# hub75-Adapter_mkii.net
KiCad netlist of a schematic drawn in EAGLE
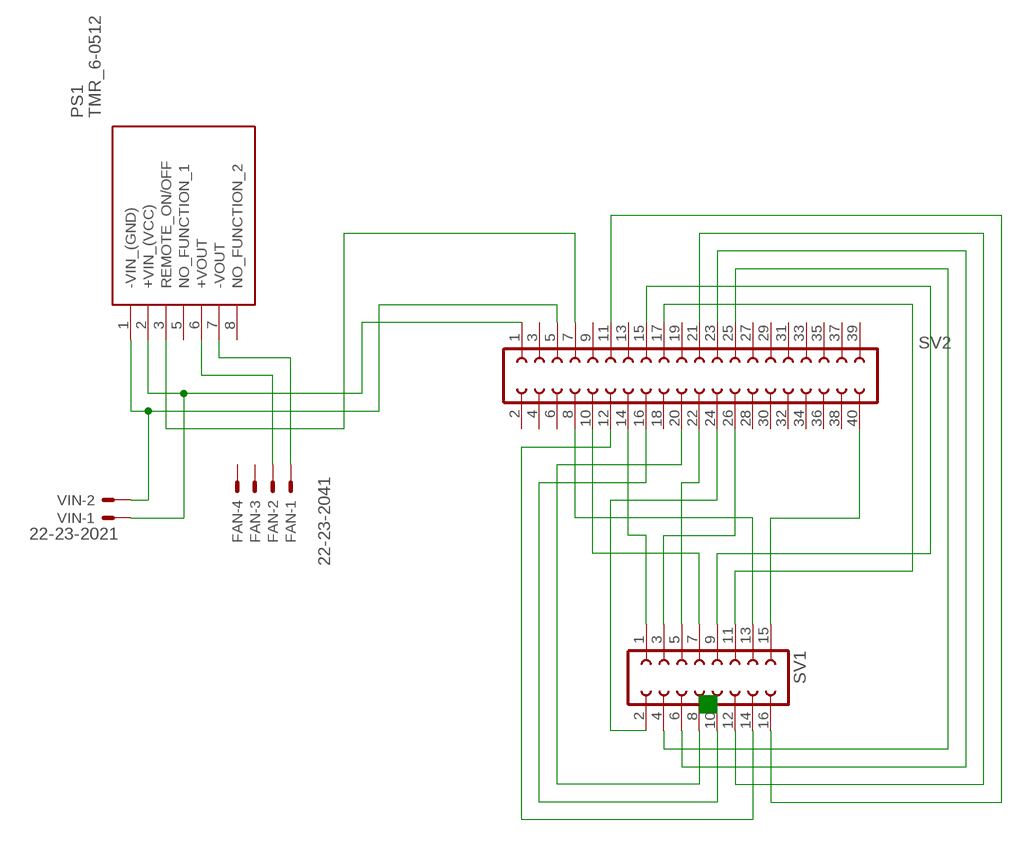
[diagram p0: schematic, sheet 1]

(export (version "E")
  (design (tool "Eeschema 10.0.6"))
  (components
    (comp (ref "FAN")
      (value "22-23-2041")
      (footprint "eagle-import:22-23-2041")
      (fields (field (name "MF") "MOLEX"))
      (libsource (lib "eagle-import") (part "22-23-2041"))
    )
    (comp (ref "PS1")
      (value "TMR_6-0512")
      (footprint "eagle-import:TMR-6")
      (fields
        (field (name "MANUFACTURER_PART_NUMBER") "TMR 6-0512")
        (field (name "MOUSER_PART_NUMBER") "495-TMR-6-0512")
      )
      (libsource (lib "eagle-import") (part "TMR_6-0512"))
    )
    (comp (ref "SV1")
      (value "FE08-2")
      (footprint "eagle-import:FE08-2")
      (libsource (lib "eagle-import") (part "FE08-2"))
    )
    (comp (ref "SV2")
      (value "FE20-2")
      (footprint "eagle-import:FE20-2")
      (libsource (lib "eagle-import") (part "FE20-2"))
    )
    (comp (ref "VIN")
      (value "22-23-2021")
      (footprint "eagle-import:22-23-2021")
      (fields (field (name "MF") "MOLEX"))
      (libsource (lib "eagle-import") (part "22-23-2021"))
    )
  )
  (nets
    (net (code "1") (name "Net-(FANA-S)") (class "Default")
      (node (ref "FAN") (pin "1") (pinfunction "S_1") (pintype "passive"))
      (node (ref "PS1") (pin "7") (pinfunction "-VOUT_7") (pintype "bidirectional"))
    )
    (net (code "2") (name "Net-(FANB-S)") (class "Default")
      (node (ref "FAN") (pin "2") (pinfunction "S_2") (pintype "passive"))
      (node (ref "PS1") (pin "6") (pinfunction "+VOUT_6") (pintype "bidirectional"))
    )
    (net (code "3") (name "Net-(PS1-+VIN_(VCC))") (class "Default")
      (node (ref "PS1") (pin "2") (pinfunction "+VIN_(VCC)_2") (pintype "bidirectional"))
      (node (ref "SV2") (pin "1") (pinfunction "1_1") (pintype "passive"))
      (node (ref "VIN") (pin "1") (pinfunction "S_1") (pintype "passive"))
    )
    (net (code "4") (name "Net-(PS1--VIN_(GND))") (class "Default")
      (node (ref "PS1") (pin "1") (pinfunction "-VIN_(GND)_1") (pintype "bidirectional"))
      (node (ref "SV2") (pin "5") (pinfunction "5_5") (pintype "passive"))
      (node (ref "VIN") (pin "2") (pinfunction "S_2") (pintype "passive"))
    )
    (net (code "5") (name "Net-(PS1-REMOTE_ON{slash}OFF)") (class "Default")
      (node (ref "PS1") (pin "3") (pinfunction "REMOTE_ON/OFF_3") (pintype "bidirectional"))
      (node (ref "SV2") (pin "7") (pinfunction "7_7") (pintype "passive"))
    )
    (net (code "6") (name "Net-(SV1-Pad1)") (class "Default")
      (node (ref "SV1") (pin "1") (pinfunction "1_1") (pintype "passive"))
      (node (ref "SV2") (pin "14") (pinfunction "14_14") (pintype "passive"))
    )
    (net (code "7") (name "Net-(SV1-Pad2)") (class "Default")
      (node (ref "SV1") (pin "2") (pinfunction "2_2") (pintype "passive"))
      (node (ref "SV2") (pin "24") (pinfunction "24_24") (pintype "passive"))
    )
    (net (code "8") (name "Net-(SV1-Pad3)") (class "Default")
      (node (ref "SV1") (pin "3") (pinfunction "3_3") (pintype "passive"))
      (node (ref "SV2") (pin "26") (pinfunction "26_26") (pintype "passive"))
    )
    (net (code "9") (name "Net-(SV1-Pad4)") (class "Default")
      (node (ref "SV1") (pin "4") (pinfunction "4_4") (pintype "passive"))
      (node (ref "SV2") (pin "25") (pinfunction "25_25") (pintype "passive"))
    )
    (net (code "10") (name "Net-(SV1-Pad5)") (class "Default")
      (node (ref "SV1") (pin "5") (pinfunction "5_5") (pintype "passive"))
      (node (ref "SV2") (pin "22") (pinfunction "22_22") (pintype "passive"))
    )
    (net (code "11") (name "Net-(SV1-Pad6)") (class "Default")
      (node (ref "SV1") (pin "6") (pinfunction "6_6") (pintype "passive"))
      (node (ref "SV2") (pin "23") (pinfunction "23_23") (pintype "passive"))
    )
    (net (code "12") (name "Net-(SV1-Pad7)") (class "Default")
      (node (ref "SV1") (pin "7") (pinfunction "7_7") (pintype "passive"))
      (node (ref "SV2") (pin "10") (pinfunction "10_10") (pintype "passive"))
    )
    (net (code "13") (name "Net-(SV1-Pad8)") (class "Default")
      (node (ref "SV1") (pin "8") (pinfunction "8_8") (pintype "passive"))
      (node (ref "SV2") (pin "20") (pinfunction "20_20") (pintype "passive"))
    )
    (net (code "14") (name "Net-(SV1-Pad9)") (class "Default")
      (node (ref "SV1") (pin "9") (pinfunction "9_9") (pintype "passive"))
      (node (ref "SV2") (pin "15") (pinfunction "15_15") (pintype "passive"))
    )
    (net (code "15") (name "Net-(SV1-Pad10)") (class "Default")
      (node (ref "SV1") (pin "10") (pinfunction "10_10") (pintype "passive"))
      (node (ref "SV2") (pin "16") (pinfunction "16_16") (pintype "passive"))
    )
    (net (code "16") (name "Net-(SV1-Pad11)") (class "Default")
      (node (ref "SV1") (pin "11") (pinfunction "11_11") (pintype "passive"))
      (node (ref "SV2") (pin "17") (pinfunction "17_17") (pintype "passive"))
    )
    (net (code "17") (name "Net-(SV1-Pad12)") (class "Default")
      (node (ref "SV1") (pin "12") (pinfunction "12_12") (pintype "passive"))
      (node (ref "SV2") (pin "21") (pinfunction "21_21") (pintype "passive"))
    )
    (net (code "18") (name "Net-(SV1-Pad13)") (class "Default")
      (node (ref "SV1") (pin "13") (pinfunction "13_13") (pintype "passive"))
      (node (ref "SV2") (pin "8") (pinfunction "8_8") (pintype "passive"))
    )
    (net (code "19") (name "Net-(SV1-Pad14)") (class "Default")
      (node (ref "SV1") (pin "14") (pinfunction "14_14") (pintype "passive"))
      (node (ref "SV2") (pin "12") (pinfunction "12_12") (pintype "passive"))
    )
    (net (code "20") (name "Net-(SV1-Pad15)") (class "Default")
      (node (ref "SV1") (pin "15") (pinfunction "15_15") (pintype "passive"))
      (node (ref "SV2") (pin "40") (pinfunction "40_40") (pintype "passive"))
    )
    (net (code "21") (name "Net-(SV1-Pad16)") (class "Default")
      (node (ref "SV1") (pin "16") (pinfunction "16_16") (pintype "passive"))
      (node (ref "SV2") (pin "11") (pinfunction "11_11") (pintype "passive"))
    )
    (net (code "22") (name "unconnected-(FANC-S-Pad3)") (class "Default")
      (node (ref "FAN") (pin "3") (pinfunction "S_3") (pintype "passive"))
    )
    (net (code "23") (name "unconnected-(FAND-S-Pad4)") (class "Default")
      (node (ref "FAN") (pin "4") (pinfunction "S_4") (pintype "passive"))
    )
    (net (code "24") (name "unconnected-(PS1-NO_FUNCTION_1-Pad5)") (class "Default")
      (node (ref "PS1") (pin "5") (pinfunction "NO_FUNCTION_1_5") (pintype "bidirectional"))
    )
    (net (code "25") (name "unconnected-(PS1-NO_FUNCTION_2-Pad8)") (class "Default")
      (node (ref "PS1") (pin "8") (pinfunction "NO_FUNCTION_2_8") (pintype "bidirectional"))
    )
    (net (code "26") (name "unconnected-(SV2-Pad2)") (class "Default")
      (node (ref "SV2") (pin "2") (pinfunction "2_2") (pintype "passive"))
    )
    (net (code "27") (name "unconnected-(SV2-Pad3)") (class "Default")
      (node (ref "SV2") (pin "3") (pinfunction "3_3") (pintype "passive"))
    )
    (net (code "28") (name "unconnected-(SV2-Pad4)") (class "Default")
      (node (ref "SV2") (pin "4") (pinfunction "4_4") (pintype "passive"))
    )
    (net (code "29") (name "unconnected-(SV2-Pad6)") (class "Default")
      (node (ref "SV2") (pin "6") (pinfunction "6_6") (pintype "passive"))
    )
    (net (code "30") (name "unconnected-(SV2-Pad9)") (class "Default")
      (node (ref "SV2") (pin "9") (pinfunction "9_9") (pintype "passive"))
    )
    (net (code "31") (name "unconnected-(SV2-Pad13)") (class "Default")
      (node (ref "SV2") (pin "13") (pinfunction "13_13") (pintype "passive"))
    )
    (net (code "32") (name "unconnected-(SV2-Pad18)") (class "Default")
      (node (ref "SV2") (pin "18") (pinfunction "18_18") (pintype "passive"))
    )
    (net (code "33") (name "unconnected-(SV2-Pad19)") (class "Default")
      (node (ref "SV2") (pin "19") (pinfunction "19_19") (pintype "passive"))
    )
    (net (code "34") (name "unconnected-(SV2-Pad27)") (class "Default")
      (node (ref "SV2") (pin "27") (pinfunction "27_27") (pintype "passive"))
    )
    (net (code "35") (name "unconnected-(SV2-Pad28)") (class "Default")
      (node (ref "SV2") (pin "28") (pinfunction "28_28") (pintype "passive"))
    )
    (net (code "36") (name "unconnected-(SV2-Pad29)") (class "Default")
      (node (ref "SV2") (pin "29") (pinfunction "29_29") (pintype "passive"))
    )
    (net (code "37") (name "unconnected-(SV2-Pad30)") (class "Default")
      (node (ref "SV2") (pin "30") (pinfunction "30_30") (pintype "passive"))
    )
    (net (code "38") (name "unconnected-(SV2-Pad31)") (class "Default")
      (node (ref "SV2") (pin "31") (pinfunction "31_31") (pintype "passive"))
    )
    (net (code "39") (name "unconnected-(SV2-Pad32)") (class "Default")
      (node (ref "SV2") (pin "32") (pinfunction "32_32") (pintype "passive"))
    )
    (net (code "40") (name "unconnected-(SV2-Pad33)") (class "Default")
      (node (ref "SV2") (pin "33") (pinfunction "33_33") (pintype "passive"))
    )
    (net (code "41") (name "unconnected-(SV2-Pad34)") (class "Default")
      (node (ref "SV2") (pin "34") (pinfunction "34_34") (pintype "passive"))
    )
    (net (code "42") (name "unconnected-(SV2-Pad35)") (class "Default")
      (node (ref "SV2") (pin "35") (pinfunction "35_35") (pintype "passive"))
    )
    (net (code "43") (name "unconnected-(SV2-Pad36)") (class "Default")
      (node (ref "SV2") (pin "36") (pinfunction "36_36") (pintype "passive"))
    )
    (net (code "44") (name "unconnected-(SV2-Pad37)") (class "Default")
      (node (ref "SV2") (pin "37") (pinfunction "37_37") (pintype "passive"))
    )
    (net (code "45") (name "unconnected-(SV2-Pad38)") (class "Default")
      (node (ref "SV2") (pin "38") (pinfunction "38_38") (pintype "passive"))
    )
    (net (code "46") (name "unconnected-(SV2-Pad39)") (class "Default")
      (node (ref "SV2") (pin "39") (pinfunction "39_39") (pintype "passive"))
    )
  )
)
